# TopLevelDesign.net
KiCad netlist of a schematic drawn in Altium Designer
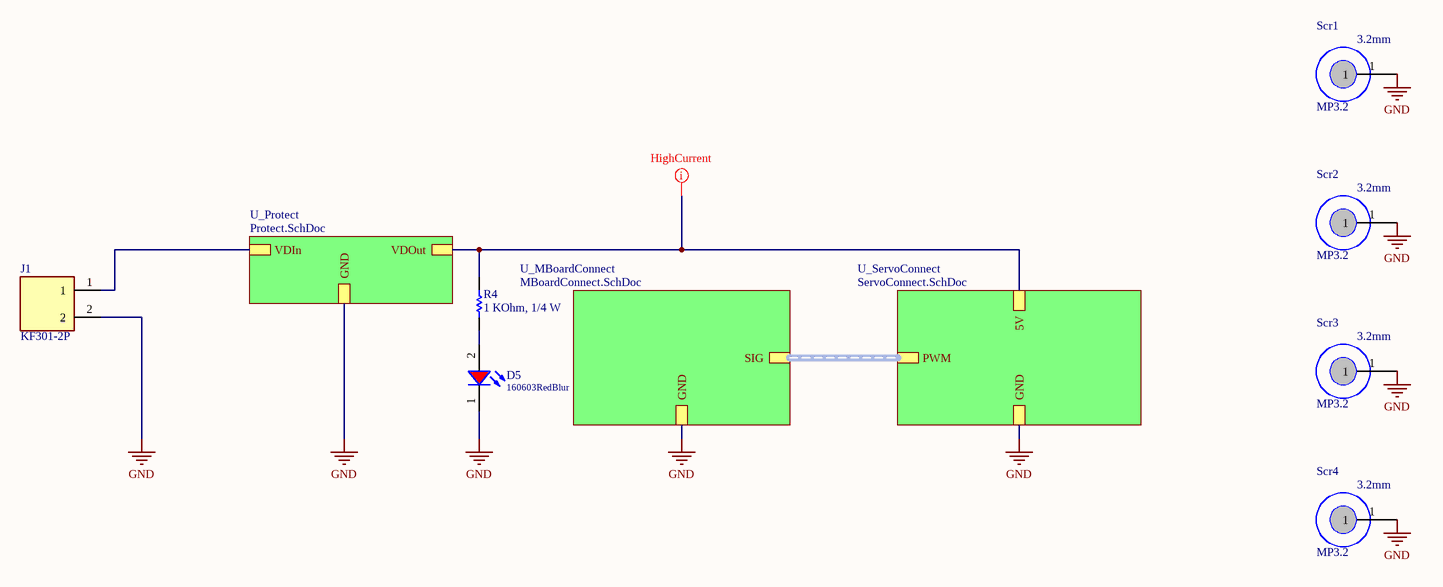
[diagram p0: TopLevelDesign.SchDoc]

(export (version "E")
  (design (tool "Eeschema 10.0.6"))
  (components
    (comp (ref "D5")
      (value "160603RedBlur")
      (footprint "WL-SMCW_0603_H=0.7mm")
      (description "WL-SMCW SMT Mono-color Chip LED Blur, size 0603, Red, 2V, 140deg")
      (libsource (lib "Tin Tran") (part "160603RedClear"))
    )
    (comp (ref "J1")
      (value "KF301-2P")
      (footprint "HANDSON_KF301-2P")
      (description "2 Pin Terminal Block 5mm Pitch")
      (libsource (lib "Tin Tran") (part "KF301-2P"))
    )
    (comp (ref "R4")
      (value "1 KOhm, 1/4 W")
      (footprint "resistor_0603")
      (description "RES, size 0603, 1 KOhm, 1/4 W")
      (fields (field (name "Comment") "0006031021"))
      (libsource (lib "Tin Tran") (part "00060371541"))
    )
    (comp (ref "Scr1") (value "MP3.2") (footprint "MP3.2") (libsource (lib "Tin Tran") (part "MP3.2")))
    (comp (ref "Scr2") (value "MP3.2") (footprint "MP3.2") (libsource (lib "Tin Tran") (part "MP3.2")))
    (comp (ref "Scr3") (value "MP3.2") (footprint "MP3.2") (libsource (lib "Tin Tran") (part "MP3.2")))
    (comp (ref "Scr4") (value "MP3.2") (footprint "MP3.2") (libsource (lib "Tin Tran") (part "MP3.2")))
  )
  (nets
    (net (code "1") (name "/5V") (class "Default")
      (node (ref "R4") (pin "2") (pinfunction "2_2") (pintype "passive"))
    )
    (net (code "3") (name "/VDIn") (class "Default")
      (node (ref "J1") (pin "1") (pinfunction "1_1") (pintype "passive"))
    )
    (net (code "4") (name "GND") (class "Default")
      (node (ref "D5") (pin "1") (pinfunction "K_1") (pintype "passive"))
      (node (ref "J1") (pin "2") (pinfunction "2_2") (pintype "passive"))
      (node (ref "Scr1") (pin "1") (pinfunction "1_1") (pintype "passive"))
      (node (ref "Scr2") (pin "1") (pinfunction "1_1") (pintype "passive"))
      (node (ref "Scr3") (pin "1") (pinfunction "1_1") (pintype "passive"))
      (node (ref "Scr4") (pin "1") (pinfunction "1_1") (pintype "passive"))
    )
    (net (code "5") (name "Net-(D5-A)") (class "Default")
      (node (ref "D5") (pin "2") (pinfunction "A_2") (pintype "passive"))
      (node (ref "R4") (pin "1") (pinfunction "1_1") (pintype "passive"))
    )
  )
)
